# tempThermostat.net
KiCad netlist of a schematic drawn in EAGLE
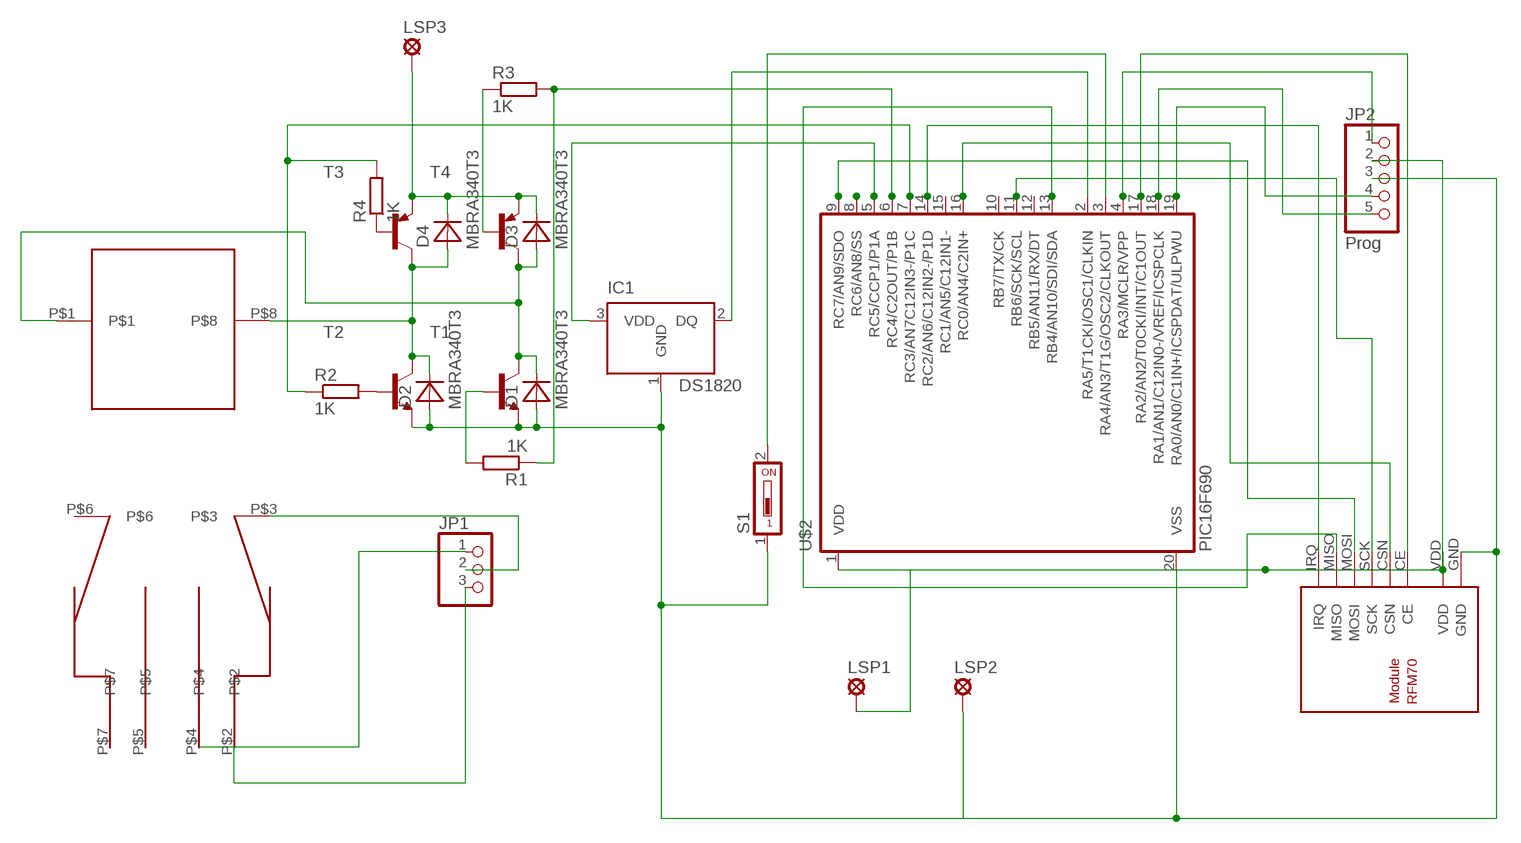
[diagram p0: schematic, sheet 1]

(export (version "E")
  (design (tool "Eeschema 10.0.6"))
  (components
    (comp (ref "D1")
      (value "MBRA340T3")
      (footprint "eagle-import:SMA")
      (libsource (lib "eagle-import") (part "MBRA340T3"))
    )
    (comp (ref "D2")
      (value "MBRA340T3")
      (footprint "eagle-import:SMA")
      (libsource (lib "eagle-import") (part "MBRA340T3"))
    )
    (comp (ref "D3")
      (value "MBRA340T3")
      (footprint "eagle-import:SMA")
      (libsource (lib "eagle-import") (part "MBRA340T3"))
    )
    (comp (ref "D4")
      (value "MBRA340T3")
      (footprint "eagle-import:SMA")
      (libsource (lib "eagle-import") (part "MBRA340T3"))
    )
    (comp (ref "IC1")
      (value "DS1820")
      (footprint "eagle-import:TO-92")
      (libsource (lib "eagle-import") (part "DS1820"))
    )
    (comp (ref "JP1")
      (value "PINHD-1X3")
      (footprint "eagle-import:1X03")
      (libsource (lib "eagle-import") (part "PINHD-1X3"))
    )
    (comp (ref "JP2")
      (value "Prog")
      (footprint "eagle-import:1X05")
      (libsource (lib "eagle-import") (part "PINHD-1X5"))
    )
    (comp (ref "LSP1")
      (value "LSP11")
      (footprint "eagle-import:LSP11")
      (libsource (lib "eagle-import") (part "LSP11"))
    )
    (comp (ref "LSP2")
      (value "LSP11")
      (footprint "eagle-import:LSP11")
      (libsource (lib "eagle-import") (part "LSP11"))
    )
    (comp (ref "LSP3")
      (value "LSP11")
      (footprint "eagle-import:LSP11")
      (libsource (lib "eagle-import") (part "LSP11"))
    )
    (comp (ref "R1")
      (value "1K")
      (footprint "eagle-import:R1206")
      (libsource (lib "eagle-import") (part "R-EU_R1206"))
    )
    (comp (ref "R2")
      (value "1K")
      (footprint "eagle-import:R1206")
      (libsource (lib "eagle-import") (part "R-EU_R1206"))
    )
    (comp (ref "R3")
      (value "1K")
      (footprint "eagle-import:R1206")
      (libsource (lib "eagle-import") (part "R-EU_R1206"))
    )
    (comp (ref "R4")
      (value "1K")
      (footprint "eagle-import:R1206")
      (libsource (lib "eagle-import") (part "R-EU_R1206"))
    )
    (comp (ref "S1")
      (value "SD4-01")
      (footprint "eagle-import:SD4-01")
      (libsource (lib "eagle-import") (part "SD4-01"))
    )
    (comp (ref "T1")
      (value "BC817-40-NPN-SOT23-BEC")
      (footprint "eagle-import:SOT23-BEC")
      (libsource (lib "eagle-import") (part "-NPN-SOT23-BECBC817-40"))
    )
    (comp (ref "T2")
      (value "BC817-40-NPN-SOT23-BEC")
      (footprint "eagle-import:SOT23-BEC")
      (libsource (lib "eagle-import") (part "-NPN-SOT23-BECBC817-40"))
    )
    (comp (ref "T3")
      (value "BC807-16-PNP-SOT23-BEC")
      (footprint "eagle-import:SOT23-BEC")
      (libsource (lib "eagle-import") (part "-PNP-SOT23-BECBC807-16"))
    )
    (comp (ref "T4")
      (value "BC807-16-PNP-SOT23-BEC")
      (footprint "eagle-import:SOT23-BEC")
      (libsource (lib "eagle-import") (part "-PNP-SOT23-BECBC807-16"))
    )
    (comp (ref "U$1")
      (value "RFM70")
      (footprint "eagle-import:RFM70")
      (libsource (lib "eagle-import") (part "RFM70"))
    )
    (comp (ref "U$2")
      (value "PIC16F690")
      (footprint "eagle-import:SSOP20")
      (libsource (lib "eagle-import") (part "PIC16F690"))
    )
    (comp (ref "U$3")
      (value "RELAYBISTABILDIP")
      (footprint "eagle-import:DIP")
      (libsource (lib "eagle-import") (part "RELAYBISTABILDIP"))
    )
  )
  (nets
    (net (code "1") (name "Net-(D1-PadC)") (class "Default")
      (node (ref "D1") (pin "C") (pinfunction "C_C") (pintype "passive"))
      (node (ref "D3") (pin "A") (pinfunction "A_A") (pintype "passive"))
      (node (ref "T1") (pin "C") (pinfunction "C_C") (pintype "passive"))
      (node (ref "T4") (pin "C") (pinfunction "C_C") (pintype "passive"))
      (node (ref "U$3") (pin "P$1") (pinfunction "P$1_P$1") (pintype "bidirectional"))
    )
    (net (code "2") (name "Net-(D2-PadC)") (class "Default")
      (node (ref "D2") (pin "C") (pinfunction "C_C") (pintype "passive"))
      (node (ref "D4") (pin "A") (pinfunction "A_A") (pintype "passive"))
      (node (ref "T2") (pin "C") (pinfunction "C_C") (pintype "passive"))
      (node (ref "T3") (pin "C") (pinfunction "C_C") (pintype "passive"))
      (node (ref "U$3") (pin "P$8") (pinfunction "P$8_P$8") (pintype "bidirectional"))
    )
    (net (code "3") (name "Net-(D3-PadC)") (class "Default")
      (node (ref "D3") (pin "C") (pinfunction "C_C") (pintype "passive"))
      (node (ref "D4") (pin "C") (pinfunction "C_C") (pintype "passive"))
      (node (ref "LSP3") (pin "MP") (pinfunction "MP_MP") (pintype "passive"))
      (node (ref "T3") (pin "E") (pinfunction "E_E") (pintype "passive"))
      (node (ref "T4") (pin "E") (pinfunction "E_E") (pintype "passive"))
    )
    (net (code "4") (name "Net-(IC1-DQ)") (class "Default")
      (node (ref "IC1") (pin "2") (pinfunction "DQ_2") (pintype "output"))
      (node (ref "U$2") (pin "2") (pinfunction "RA5/T1CKI/OSC1/CLKIN_2") (pintype "bidirectional"))
    )
    (net (code "5") (name "Net-(IC1-GND)") (class "Default")
      (node (ref "D1") (pin "A") (pinfunction "A_A") (pintype "passive"))
      (node (ref "D2") (pin "A") (pinfunction "A_A") (pintype "passive"))
      (node (ref "IC1") (pin "1") (pinfunction "GND_1") (pintype "power_in"))
      (node (ref "JP2") (pin "3") (pinfunction "3_3") (pintype "passive"))
      (node (ref "LSP2") (pin "MP") (pinfunction "MP_MP") (pintype "passive"))
      (node (ref "S1") (pin "1") (pinfunction "1_1") (pintype "passive"))
      (node (ref "T1") (pin "E") (pinfunction "E_E") (pintype "passive"))
      (node (ref "T2") (pin "E") (pinfunction "E_E") (pintype "passive"))
      (node (ref "U$1") (pin "GND") (pinfunction "GND_GND") (pintype "power_in"))
      (node (ref "U$2") (pin "20") (pinfunction "VSS_20") (pintype "power_in"))
    )
    (net (code "6") (name "Net-(IC1-VDD)") (class "Default")
      (node (ref "IC1") (pin "3") (pinfunction "VDD_3") (pintype "input"))
      (node (ref "U$2") (pin "5") (pinfunction "RC5/CCP1/P1A_5") (pintype "bidirectional"))
    )
    (net (code "7") (name "Net-(JP1-Pad1)") (class "Default")
      (node (ref "JP1") (pin "1") (pinfunction "1_1") (pintype "passive"))
      (node (ref "U$3") (pin "P$4") (pinfunction "P$4_P$4") (pintype "bidirectional"))
    )
    (net (code "8") (name "Net-(JP1-Pad2)") (class "Default")
      (node (ref "JP1") (pin "2") (pinfunction "2_2") (pintype "passive"))
      (node (ref "U$3") (pin "P$3") (pinfunction "P$3_P$3") (pintype "bidirectional"))
    )
    (net (code "9") (name "Net-(JP1-Pad3)") (class "Default")
      (node (ref "JP1") (pin "3") (pinfunction "3_3") (pintype "passive"))
      (node (ref "U$3") (pin "P$2") (pinfunction "P$2_P$2") (pintype "bidirectional"))
    )
    (net (code "10") (name "Net-(R1-Pad2)") (class "Default")
      (node (ref "R1") (pin "2") (pinfunction "2_2") (pintype "passive"))
      (node (ref "T1") (pin "B") (pinfunction "B_B") (pintype "passive"))
    )
    (net (code "11") (name "Net-(R2-Pad2)") (class "Default")
      (node (ref "R2") (pin "2") (pinfunction "2_2") (pintype "passive"))
      (node (ref "T2") (pin "B") (pinfunction "B_B") (pintype "passive"))
    )
    (net (code "12") (name "Net-(R3-Pad1)") (class "Default")
      (node (ref "R3") (pin "1") (pinfunction "1_1") (pintype "passive"))
      (node (ref "T4") (pin "B") (pinfunction "B_B") (pintype "passive"))
    )
    (net (code "13") (name "Net-(R4-Pad1)") (class "Default")
      (node (ref "R4") (pin "1") (pinfunction "1_1") (pintype "passive"))
      (node (ref "T3") (pin "B") (pinfunction "B_B") (pintype "passive"))
    )
    (net (code "14") (name "Net-(U$2-RA0{slash}AN0{slash}C1IN+{slash}ICSPDAT{slash}ULPWU)") (class "Default")
      (node (ref "JP2") (pin "4") (pinfunction "4_4") (pintype "passive"))
      (node (ref "U$2") (pin "19") (pinfunction "RA0/AN0/C1IN+/ICSPDAT/ULPWU_19") (pintype "bidirectional"))
    )
    (net (code "15") (name "Net-(U$2-RA1{slash}AN1{slash}C12IN0-{slash}VREF{slash}ICSPCLK)") (class "Default")
      (node (ref "JP2") (pin "5") (pinfunction "5_5") (pintype "passive"))
      (node (ref "U$2") (pin "18") (pinfunction "RA1/AN1/C12IN0-/VREF/ICSPCLK_18") (pintype "bidirectional"))
    )
    (net (code "16") (name "Net-(U$2-RA2{slash}AN2{slash}T0CKI{slash}INT{slash}C1OUT)") (class "Default")
      (node (ref "U$1") (pin "CE") (pinfunction "CE_CE") (pintype "bidirectional"))
      (node (ref "U$2") (pin "17") (pinfunction "RA2/AN2/T0CKI/INT/C1OUT_17") (pintype "bidirectional"))
    )
    (net (code "17") (name "Net-(U$2-RA3{slash}MCLR{slash}VPP)") (class "Default")
      (node (ref "JP2") (pin "1") (pinfunction "1_1") (pintype "passive"))
      (node (ref "U$2") (pin "4") (pinfunction "RA3/MCLR/VPP_4") (pintype "bidirectional"))
    )
    (net (code "18") (name "Net-(U$2-RA4{slash}AN3{slash}T1G{slash}OSC2{slash}CLKOUT)") (class "Default")
      (node (ref "S1") (pin "2") (pinfunction "2_2") (pintype "passive"))
      (node (ref "U$2") (pin "3") (pinfunction "RA4/AN3/T1G/OSC2/CLKOUT_3") (pintype "bidirectional"))
    )
    (net (code "19") (name "Net-(U$2-RB4{slash}AN10{slash}SDI{slash}SDA)") (class "Default")
      (node (ref "U$1") (pin "MISO") (pinfunction "MISO_MISO") (pintype "bidirectional"))
      (node (ref "U$2") (pin "13") (pinfunction "RB4/AN10/SDI/SDA_13") (pintype "bidirectional"))
    )
    (net (code "20") (name "Net-(U$2-RB6{slash}SCK{slash}SCL)") (class "Default")
      (node (ref "U$1") (pin "SCK") (pinfunction "SCK_SCK") (pintype "bidirectional"))
      (node (ref "U$2") (pin "11") (pinfunction "RB6/SCK/SCL_11") (pintype "bidirectional"))
    )
    (net (code "21") (name "Net-(U$2-RC0{slash}AN4{slash}C2IN+)") (class "Default")
      (node (ref "U$1") (pin "CSN") (pinfunction "CSN_CSN") (pintype "bidirectional"))
      (node (ref "U$2") (pin "16") (pinfunction "RC0/AN4/C2IN+_16") (pintype "bidirectional"))
    )
    (net (code "22") (name "Net-(U$2-RC2{slash}AN6{slash}C12IN2-{slash}P1D)") (class "Default")
      (node (ref "U$1") (pin "IRQ") (pinfunction "IRQ_IRQ") (pintype "bidirectional"))
      (node (ref "U$2") (pin "14") (pinfunction "RC2/AN6/C12IN2-/P1D_14") (pintype "bidirectional"))
    )
    (net (code "23") (name "Net-(U$2-RC3{slash}AN7C12IN3-{slash}P1C)") (class "Default")
      (node (ref "R2") (pin "1") (pinfunction "1_1") (pintype "passive"))
      (node (ref "R4") (pin "2") (pinfunction "2_2") (pintype "passive"))
      (node (ref "U$2") (pin "7") (pinfunction "RC3/AN7C12IN3-/P1C_7") (pintype "bidirectional"))
    )
    (net (code "24") (name "Net-(U$2-RC4{slash}C2OUT{slash}P1B)") (class "Default")
      (node (ref "R1") (pin "1") (pinfunction "1_1") (pintype "passive"))
      (node (ref "R3") (pin "2") (pinfunction "2_2") (pintype "passive"))
      (node (ref "U$2") (pin "6") (pinfunction "RC4/C2OUT/P1B_6") (pintype "bidirectional"))
    )
    (net (code "25") (name "Net-(U$2-RC7{slash}AN9{slash}SDO)") (class "Default")
      (node (ref "U$1") (pin "MOSI") (pinfunction "MOSI_MOSI") (pintype "bidirectional"))
      (node (ref "U$2") (pin "9") (pinfunction "RC7/AN9/SDO_9") (pintype "bidirectional"))
    )
    (net (code "26") (name "Net-(U$2-VDD)") (class "Default")
      (node (ref "JP2") (pin "2") (pinfunction "2_2") (pintype "passive"))
      (node (ref "LSP1") (pin "MP") (pinfunction "MP_MP") (pintype "passive"))
      (node (ref "U$1") (pin "VDD") (pinfunction "VDD_VDD") (pintype "power_in"))
      (node (ref "U$2") (pin "1") (pinfunction "VDD_1") (pintype "power_in"))
    )
    (net (code "27") (name "unconnected-(U$2-RB5{slash}AN11{slash}RX{slash}DT-Pad12)") (class "Default")
      (node (ref "U$2") (pin "12") (pinfunction "RB5/AN11/RX/DT_12") (pintype "bidirectional"))
    )
    (net (code "28") (name "unconnected-(U$2-RB7{slash}TX{slash}CK-Pad10)") (class "Default")
      (node (ref "U$2") (pin "10") (pinfunction "RB7/TX/CK_10") (pintype "bidirectional"))
    )
    (net (code "29") (name "unconnected-(U$2-RC1{slash}AN5{slash}C12IN1--Pad15)") (class "Default")
      (node (ref "U$2") (pin "15") (pinfunction "RC1/AN5/C12IN1-_15") (pintype "bidirectional"))
    )
    (net (code "30") (name "unconnected-(U$2-RC6{slash}AN8{slash}SS-Pad8)") (class "Default")
      (node (ref "U$2") (pin "8") (pinfunction "RC6/AN8/SS_8") (pintype "bidirectional"))
    )
    (net (code "31") (name "unconnected-(U$3-PadP$5)") (class "Default")
      (node (ref "U$3") (pin "P$5") (pinfunction "P$5_P$5") (pintype "bidirectional"))
    )
    (net (code "32") (name "unconnected-(U$3-PadP$6)") (class "Default")
      (node (ref "U$3") (pin "P$6") (pinfunction "P$6_P$6") (pintype "bidirectional"))
    )
    (net (code "33") (name "unconnected-(U$3-PadP$7)") (class "Default")
      (node (ref "U$3") (pin "P$7") (pinfunction "P$7_P$7") (pintype "bidirectional"))
    )
  )
)
